# Digi_PID_Cltr.net
KiCad netlist of a schematic drawn in Altium Designer
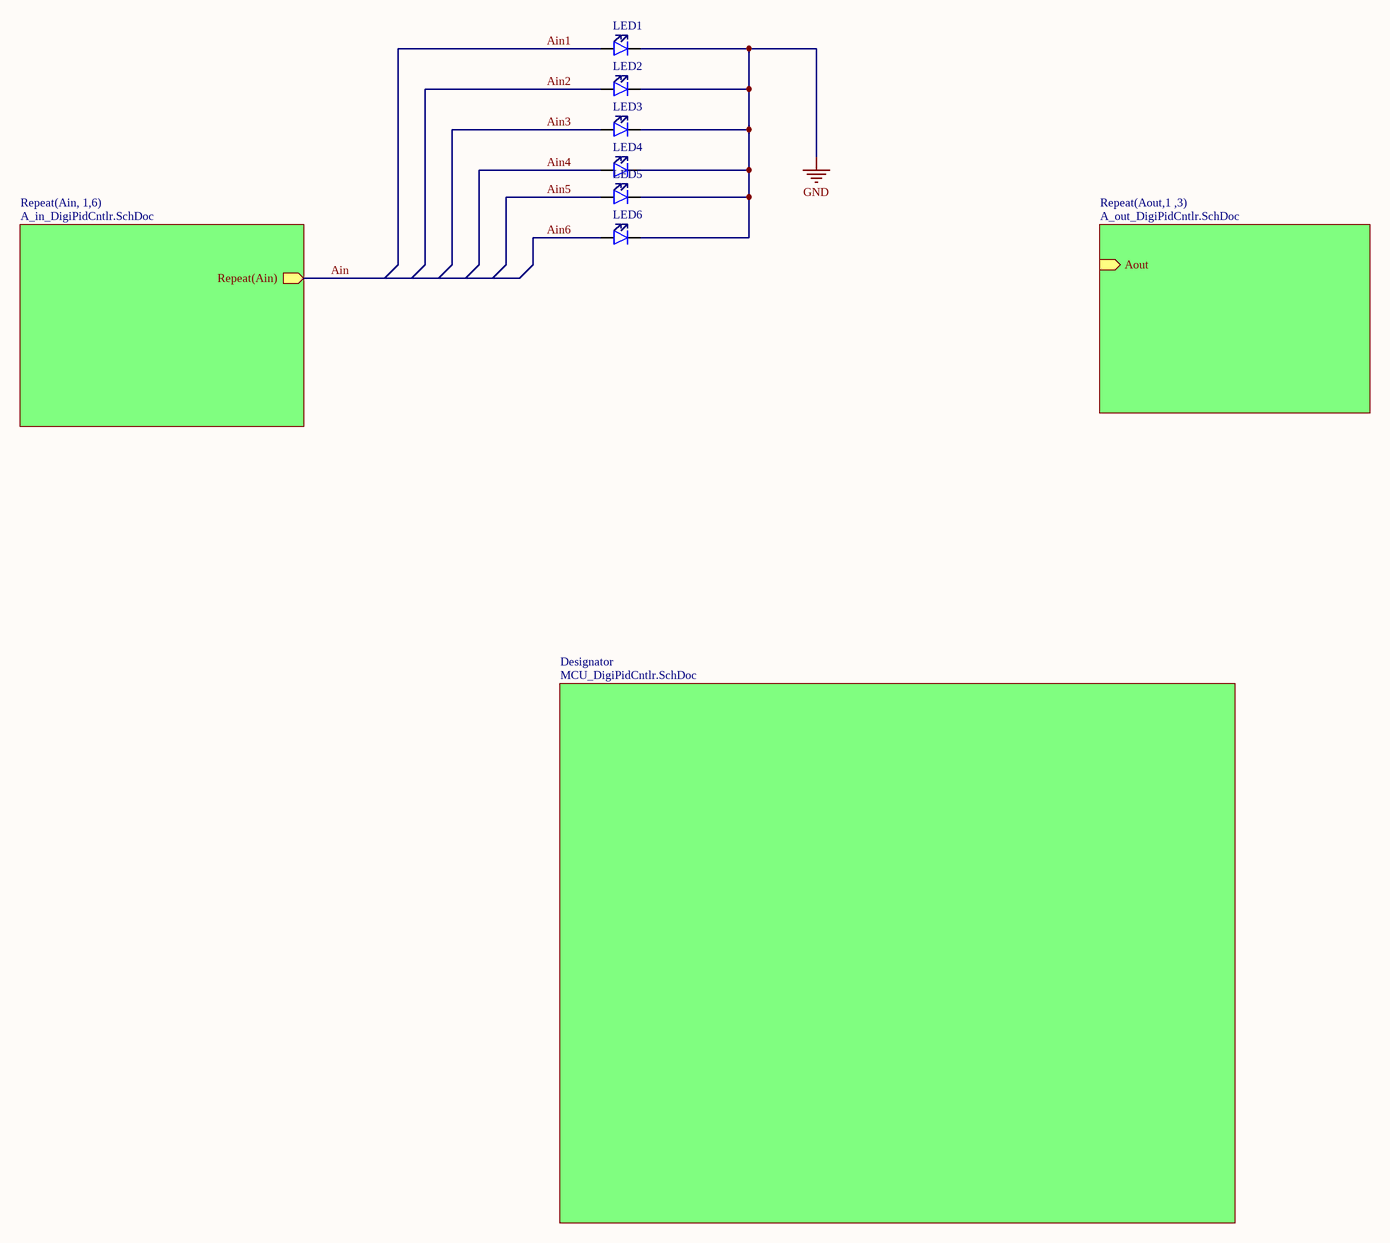
[diagram p0: Digi_PID_Cltr.SchDoc]

(export (version "E")
  (design (tool "Eeschema 10.0.6"))
  (components
    (comp (ref "LED1") (value "LED") (footprint "SMD LED 0805") (libsource (lib "LED") (part "LED")))
    (comp (ref "LED2") (value "LED") (footprint "SMD LED 0805") (libsource (lib "LED") (part "LED")))
    (comp (ref "LED3") (value "LED") (footprint "SMD LED 0805") (libsource (lib "LED") (part "LED")))
    (comp (ref "LED4") (value "LED") (footprint "SMD LED 0805") (libsource (lib "LED") (part "LED")))
    (comp (ref "LED5") (value "LED") (footprint "SMD LED 0805") (libsource (lib "LED") (part "LED")))
    (comp (ref "LED6") (value "LED") (footprint "SMD LED 0805") (libsource (lib "LED") (part "LED")))
  )
  (nets
    (net (code "1") (name "/Ain") (class "Default")
      (node (ref "LED6") (pin "A") (pinfunction "A_A") (pintype "passive"))
    )
    (net (code "2") (name "/Ain1") (class "Default")
      (node (ref "LED1") (pin "A") (pinfunction "A_A") (pintype "passive"))
    )
    (net (code "3") (name "/Ain2") (class "Default")
      (node (ref "LED2") (pin "A") (pinfunction "A_A") (pintype "passive"))
    )
    (net (code "4") (name "/Ain3") (class "Default")
      (node (ref "LED3") (pin "A") (pinfunction "A_A") (pintype "passive"))
    )
    (net (code "5") (name "/Ain4") (class "Default")
      (node (ref "LED4") (pin "A") (pinfunction "A_A") (pintype "passive"))
    )
    (net (code "6") (name "/Ain5") (class "Default")
      (node (ref "LED5") (pin "A") (pinfunction "A_A") (pintype "passive"))
    )
    (net (code "8") (name "GND") (class "Default")
      (node (ref "LED1") (pin "K") (pinfunction "K_K") (pintype "passive"))
      (node (ref "LED2") (pin "K") (pinfunction "K_K") (pintype "passive"))
      (node (ref "LED3") (pin "K") (pinfunction "K_K") (pintype "passive"))
      (node (ref "LED4") (pin "K") (pinfunction "K_K") (pintype "passive"))
      (node (ref "LED5") (pin "K") (pinfunction "K_K") (pintype "passive"))
      (node (ref "LED6") (pin "K") (pinfunction "K_K") (pintype "passive"))
    )
  )
)
